# Board_R2_v2.net
KiCad netlist of a schematic drawn in EAGLE
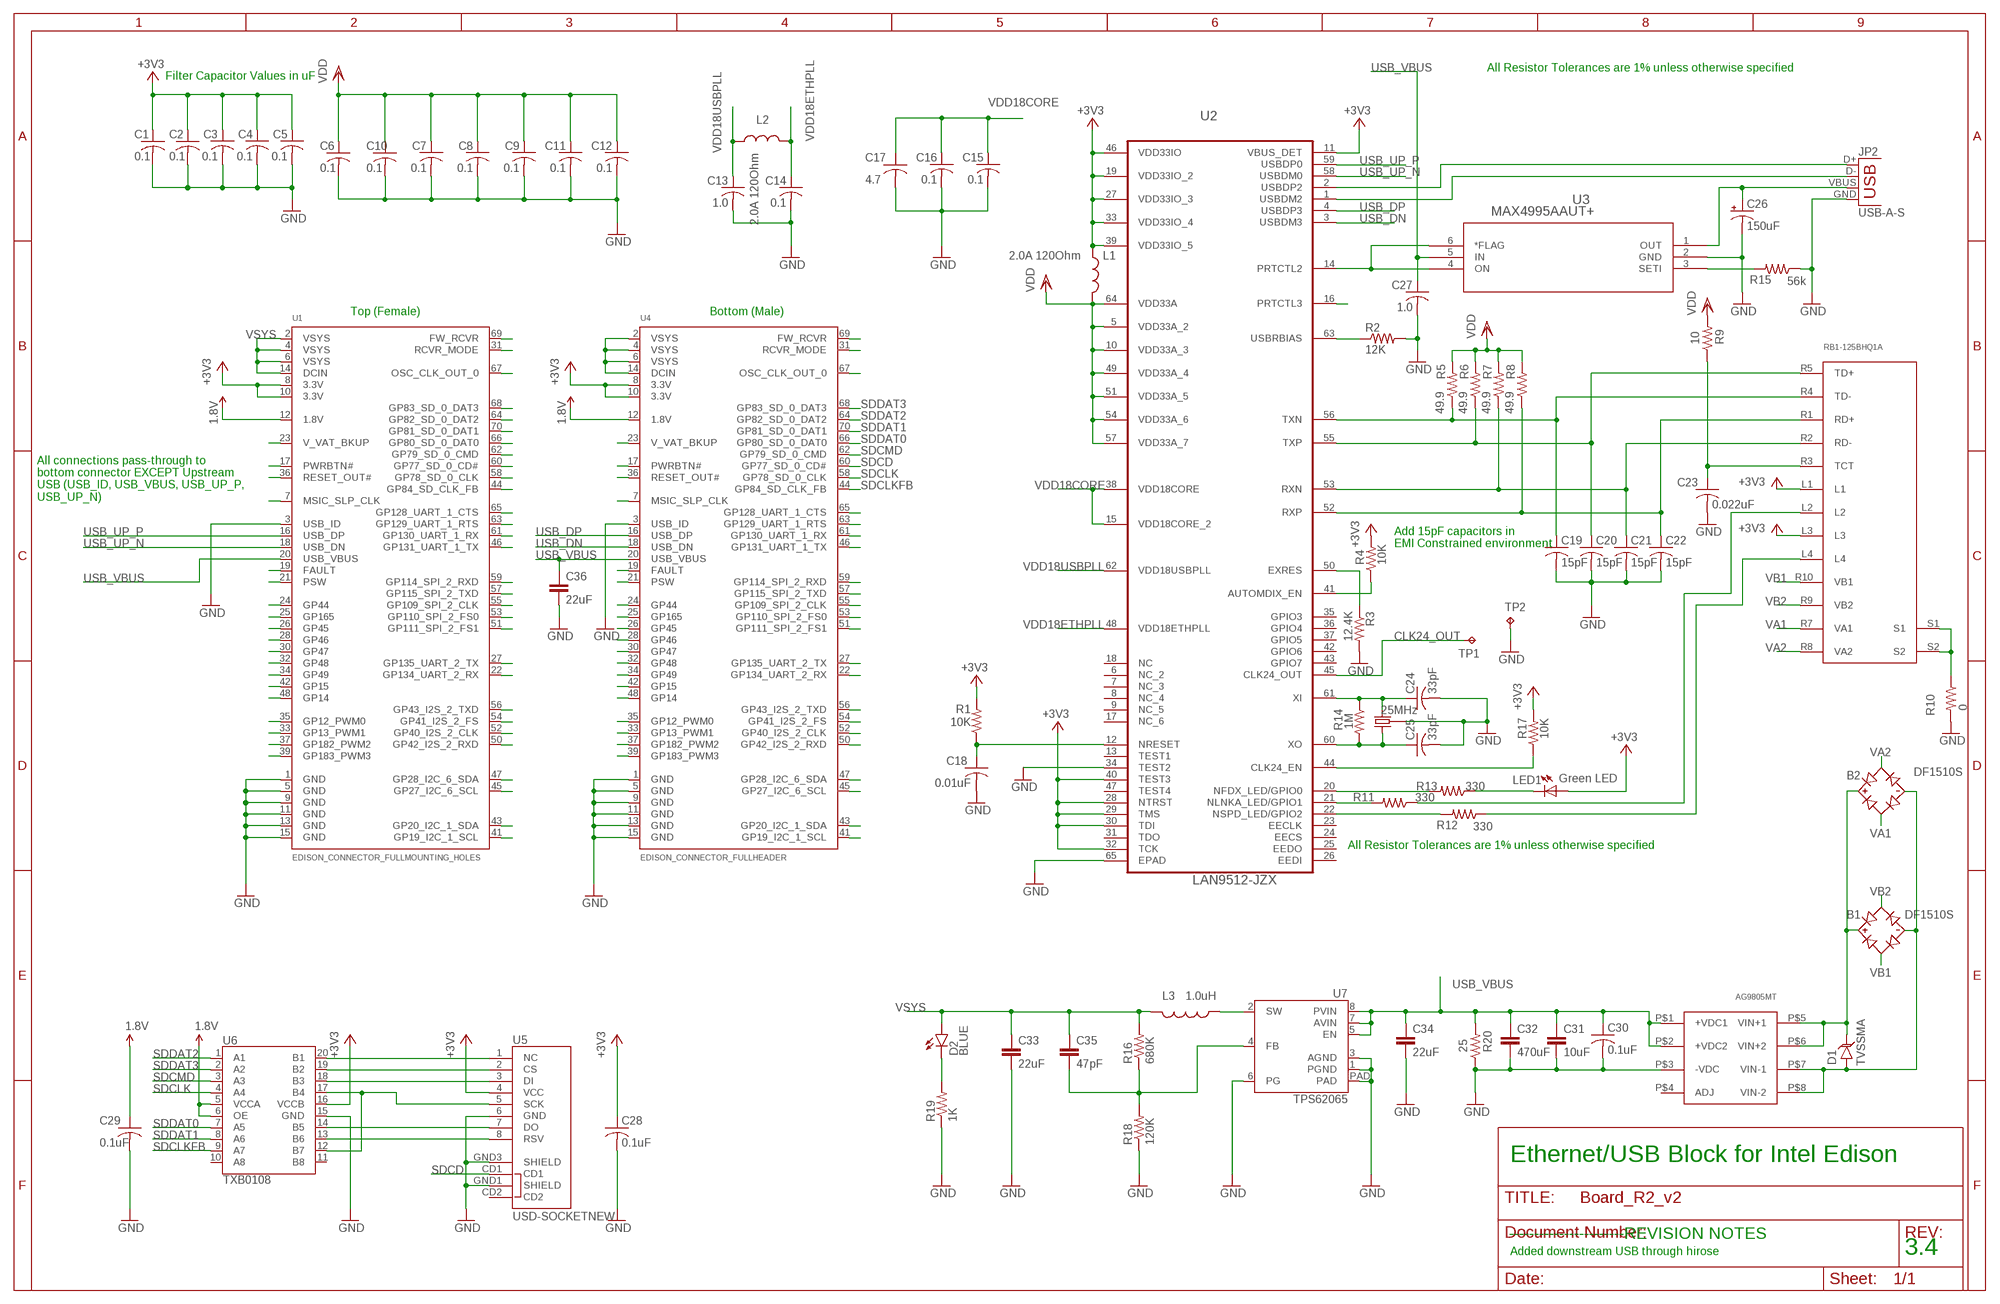
[diagram p0: schematic, sheet 1]

(export (version "E")
  (design (tool "Eeschema 10.0.6"))
  (components
    (comp (ref "AG9805MT")
      (value "AG9800M")
      (footprint "eagle-import:AG9800M_SMT")
      (libsource (lib "eagle-import") (part "AG9800M"))
    )
    (comp (ref "B1")
      (value "DF1510S")
      (footprint "eagle-import:DFS")
      (libsource (lib "eagle-import") (part "DF1510S"))
    )
    (comp (ref "B2")
      (value "DF1510S")
      (footprint "eagle-import:DFS")
      (libsource (lib "eagle-import") (part "DF1510S"))
    )
    (comp (ref "C1")
      (value "0.1")
      (footprint "eagle-import:C0402K")
      (libsource (lib "eagle-import") (part "C-USC0402K"))
    )
    (comp (ref "C2")
      (value "0.1")
      (footprint "eagle-import:C0402K")
      (libsource (lib "eagle-import") (part "C-USC0402K"))
    )
    (comp (ref "C3")
      (value "0.1")
      (footprint "eagle-import:C0402K")
      (libsource (lib "eagle-import") (part "C-USC0402K"))
    )
    (comp (ref "C4")
      (value "0.1")
      (footprint "eagle-import:C0402K")
      (libsource (lib "eagle-import") (part "C-USC0402K"))
    )
    (comp (ref "C5")
      (value "0.1")
      (footprint "eagle-import:C0402K")
      (libsource (lib "eagle-import") (part "C-USC0402K"))
    )
    (comp (ref "C6")
      (value "0.1")
      (footprint "eagle-import:C0402K")
      (libsource (lib "eagle-import") (part "C-USC0402K"))
    )
    (comp (ref "C7")
      (value "0.1")
      (footprint "eagle-import:C0402K")
      (libsource (lib "eagle-import") (part "C-USC0402K"))
    )
    (comp (ref "C8")
      (value "0.1")
      (footprint "eagle-import:C0402K")
      (libsource (lib "eagle-import") (part "C-USC0402K"))
    )
    (comp (ref "C9")
      (value "0.1")
      (footprint "eagle-import:C0402K")
      (libsource (lib "eagle-import") (part "C-USC0402K"))
    )
    (comp (ref "C10")
      (value "0.1")
      (footprint "eagle-import:C0402K")
      (libsource (lib "eagle-import") (part "C-USC0402K"))
    )
    (comp (ref "C11")
      (value "0.1")
      (footprint "eagle-import:C0402K")
      (libsource (lib "eagle-import") (part "C-USC0402K"))
    )
    (comp (ref "C12")
      (value "0.1")
      (footprint "eagle-import:C0402K")
      (libsource (lib "eagle-import") (part "C-USC0402K"))
    )
    (comp (ref "C13")
      (value "1.0")
      (footprint "eagle-import:C0402K")
      (libsource (lib "eagle-import") (part "C-USC0402K"))
    )
    (comp (ref "C14")
      (value "0.1")
      (footprint "eagle-import:C0402K")
      (libsource (lib "eagle-import") (part "C-USC0402K"))
    )
    (comp (ref "C15")
      (value "0.1")
      (footprint "eagle-import:C0402K")
      (libsource (lib "eagle-import") (part "C-USC0402K"))
    )
    (comp (ref "C16")
      (value "0.1")
      (footprint "eagle-import:C0402K")
      (libsource (lib "eagle-import") (part "C-USC0402K"))
    )
    (comp (ref "C17")
      (value "4.7")
      (footprint "eagle-import:C0603K")
      (libsource (lib "eagle-import") (part "C-USC0603K"))
    )
    (comp (ref "C18")
      (value "0.01uF")
      (footprint "eagle-import:C0603K")
      (libsource (lib "eagle-import") (part "C-USC0603K"))
    )
    (comp (ref "C19")
      (value "15pF")
      (footprint "eagle-import:C0402")
      (libsource (lib "eagle-import") (part "C-USC0402"))
    )
    (comp (ref "C20")
      (value "15pF")
      (footprint "eagle-import:C0402")
      (libsource (lib "eagle-import") (part "C-USC0402"))
    )
    (comp (ref "C21")
      (value "15pF")
      (footprint "eagle-import:C0402")
      (libsource (lib "eagle-import") (part "C-USC0402"))
    )
    (comp (ref "C22")
      (value "15pF")
      (footprint "eagle-import:C0402")
      (libsource (lib "eagle-import") (part "C-USC0402"))
    )
    (comp (ref "C23")
      (value "0.022uF")
      (footprint "eagle-import:C0805")
      (libsource (lib "eagle-import") (part "resistor_C-USC0805"))
    )
    (comp (ref "C24")
      (value "33pF")
      (footprint "eagle-import:C0402")
      (libsource (lib "eagle-import") (part "C-USC0402"))
    )
    (comp (ref "C25")
      (value "33pF")
      (footprint "eagle-import:C0402")
      (libsource (lib "eagle-import") (part "C-USC0402"))
    )
    (comp (ref "C26")
      (value "150uF")
      (footprint "eagle-import:PANASONIC_E")
      (libsource (lib "eagle-import") (part "CAP_POLE"))
    )
    (comp (ref "C27")
      (value "1.0")
      (footprint "eagle-import:C0402K")
      (libsource (lib "eagle-import") (part "C-USC0402K"))
    )
    (comp (ref "C28")
      (value "0.1uF")
      (footprint "eagle-import:C0402")
      (libsource (lib "eagle-import") (part "C-USC0402"))
    )
    (comp (ref "C29")
      (value "0.1uF")
      (footprint "eagle-import:C0402")
      (libsource (lib "eagle-import") (part "C-USC0402"))
    )
    (comp (ref "C30")
      (value "0.1uF")
      (footprint "eagle-import:C0402")
      (libsource (lib "eagle-import") (part "C-USC0402"))
    )
    (comp (ref "C31")
      (value "10uF")
      (footprint "eagle-import:1206-CAP")
      (libsource (lib "eagle-import") (part "4.7UF-16V-20%,+80%-(1206)"))
    )
    (comp (ref "C32")
      (value "470uF")
      (footprint "eagle-import:16SVPE470M")
      (libsource (lib "eagle-import") (part "F12CAP"))
    )
    (comp (ref "C33")
      (value "22uF")
      (footprint "eagle-import:0603-CAP")
      (libsource (lib "eagle-import") (part "47PF-50V-5%(0603)"))
    )
    (comp (ref "C34")
      (value "22uF")
      (footprint "eagle-import:0603-CAP")
      (libsource (lib "eagle-import") (part "47PF-50V-5%(0603)"))
    )
    (comp (ref "C35")
      (value "47pF")
      (footprint "eagle-import:0603-CAP")
      (libsource (lib "eagle-import") (part "47PF-50V-5%(0603)"))
    )
    (comp (ref "C36")
      (value "22uF")
      (footprint "eagle-import:0603-CAP")
      (libsource (lib "eagle-import") (part "47PF-50V-5%(0603)"))
    )
    (comp (ref "D1")
      (value "TVSSMA")
      (footprint "eagle-import:SMA-DIODE")
      (libsource (lib "eagle-import") (part "TVSSMA"))
    )
    (comp (ref "D2")
      (value "BLUE")
      (footprint "eagle-import:LED-0603")
      (libsource (lib "eagle-import") (part "LED-BLUE0603"))
    )
    (comp (ref "JP2")
      (value "USB-A-S")
      (footprint "eagle-import:USB-A-S")
      (libsource (lib "eagle-import") (part "USB-A-S"))
    )
    (comp (ref "L1")
      (value "2.0A 120Ohm")
      (footprint "eagle-import:L0603")
      (libsource (lib "eagle-import") (part "L-US0603"))
    )
    (comp (ref "L2")
      (value "2.0A 120Ohm")
      (footprint "eagle-import:L0603")
      (libsource (lib "eagle-import") (part "L-US0603"))
    )
    (comp (ref "L3")
      (value "1.0uH")
      (footprint "eagle-import:1210")
      (libsource (lib "eagle-import") (part "INDUCTOR1210"))
    )
    (comp (ref "LED1")
      (value "Green LED")
      (footprint "eagle-import:CHIP-LED0805")
      (libsource (lib "eagle-import") (part "LEDCHIP-LED0805"))
    )
    (comp (ref "R1")
      (value "10K")
      (footprint "eagle-import:R0603")
      (libsource (lib "eagle-import") (part "resistor_R-US_R0603"))
    )
    (comp (ref "R2")
      (value "12K")
      (footprint "eagle-import:R0603")
      (libsource (lib "eagle-import") (part "resistor_R-US_R0603"))
    )
    (comp (ref "R3")
      (value "12.4K")
      (footprint "eagle-import:R0603")
      (libsource (lib "eagle-import") (part "resistor_R-US_R0603"))
    )
    (comp (ref "R4")
      (value "10K")
      (footprint "eagle-import:R0603")
      (libsource (lib "eagle-import") (part "resistor_R-US_R0603"))
    )
    (comp (ref "R5")
      (value "49.9")
      (footprint "eagle-import:R0402")
      (libsource (lib "eagle-import") (part "resistor_R-US_R0402"))
    )
    (comp (ref "R6")
      (value "49.9")
      (footprint "eagle-import:R0402")
      (libsource (lib "eagle-import") (part "resistor_R-US_R0402"))
    )
    (comp (ref "R7")
      (value "49.9")
      (footprint "eagle-import:R0402")
      (libsource (lib "eagle-import") (part "resistor_R-US_R0402"))
    )
    (comp (ref "R8")
      (value "49.9")
      (footprint "eagle-import:R0402")
      (libsource (lib "eagle-import") (part "resistor_R-US_R0402"))
    )
    (comp (ref "R9")
      (value "10")
      (footprint "eagle-import:R0402")
      (libsource (lib "eagle-import") (part "resistor_R-US_R0402"))
    )
    (comp (ref "R10")
      (value "0")
      (footprint "eagle-import:R1210")
      (libsource (lib "eagle-import") (part "resistor_R-US_R1210"))
    )
    (comp (ref "R11")
      (value "330")
      (footprint "eagle-import:R0402")
      (libsource (lib "eagle-import") (part "resistor_R-US_R0402"))
    )
    (comp (ref "R12")
      (value "330")
      (footprint "eagle-import:R0402")
      (libsource (lib "eagle-import") (part "resistor_R-US_R0402"))
    )
    (comp (ref "R13")
      (value "330")
      (footprint "eagle-import:R0402")
      (libsource (lib "eagle-import") (part "resistor_R-US_R0402"))
    )
    (comp (ref "R14")
      (value "1M")
      (footprint "eagle-import:R0402")
      (libsource (lib "eagle-import") (part "resistor_R-US_R0402"))
    )
    (comp (ref "R15")
      (value "56k")
      (footprint "eagle-import:R0603")
      (libsource (lib "eagle-import") (part "R-US_R0603"))
    )
    (comp (ref "R16")
      (value "680K")
      (footprint "eagle-import:0402-RES")
      (libsource (lib "eagle-import") (part "RESISTOR0402"))
    )
    (comp (ref "R17")
      (value "10K")
      (footprint "eagle-import:R0603")
      (libsource (lib "eagle-import") (part "resistor_R-US_R0603"))
    )
    (comp (ref "R18")
      (value "120K")
      (footprint "eagle-import:0402-RES")
      (libsource (lib "eagle-import") (part "RESISTOR0402"))
    )
    (comp (ref "R19")
      (value "1K")
      (footprint "eagle-import:0603-RES")
      (libsource (lib "eagle-import") (part "1KOHM-1/10W-1%(0603)"))
    )
    (comp (ref "R20")
      (value "25")
      (footprint "eagle-import:R0402")
      (libsource (lib "eagle-import") (part "resistor_R-US_R0402"))
    )
    (comp (ref "RB1-125BHQ1A")
      (value "RB1-125BHQ1A")
      (footprint "eagle-import:RB1-125BHQ1A")
      (libsource (lib "eagle-import") (part "RB1-125BHQ1A"))
    )
    (comp (ref "TP1")
      (value "TPTP20R")
      (footprint "eagle-import:TP20R")
      (libsource (lib "eagle-import") (part "TPTP20R"))
    )
    (comp (ref "TP2")
      (value "TPTP20R")
      (footprint "eagle-import:TP20R")
      (libsource (lib "eagle-import") (part "TPTP20R"))
    )
    (comp (ref "U$1")
      (value "25MHz")
      (footprint "eagle-import:CRYSTAL-SMD-5X3")
      (libsource (lib "eagle-import") (part "CRYSTAL-GROUNDED"))
    )
    (comp (ref "U1")
      (value "EDISON_CONNECTOR_FULLMOUNTING_HOLES")
      (footprint "eagle-import:EDISON_DAUGHTER")
      (libsource (lib "eagle-import") (part "EDISON_CONNECTOR_FULLMOUNTING_HOLES"))
    )
    (comp (ref "U2")
      (value "LAN9512-JZX")
      (footprint "eagle-import:QFN50P900X900X100-65N")
      (libsource (lib "eagle-import") (part "LAN9512-JZX"))
    )
    (comp (ref "U3")
      (value "MAX4995AAUT+")
      (footprint "eagle-import:21-0058I")
      (fields (field (name "MANUFACTURER_PART_NUMBER") "max4995aaut+"))
      (libsource (lib "eagle-import") (part "MAX4995AAUT+"))
    )
    (comp (ref "U4")
      (value "EDISON_CONNECTOR_FULLHEADER")
      (footprint "eagle-import:DF40C-70DP-0.4(51)")
      (libsource (lib "eagle-import") (part "EDISON_CONNECTOR_FULLHEADER"))
    )
    (comp (ref "U5")
      (value "USD-SOCKETNEW")
      (footprint "eagle-import:MICRO-SD-SOCKET-PP")
      (libsource (lib "eagle-import") (part "USD-SOCKETNEW"))
    )
    (comp (ref "U6")
      (value "TXB0108")
      (footprint "eagle-import:UFDFN-20")
      (libsource (lib "eagle-import") (part "TXB0108"))
    )
    (comp (ref "U7")
      (value "TPS62065")
      (footprint "eagle-import:WSON-8-PAD")
      (libsource (lib "eagle-import") (part "TPS62065"))
    )
  )
  (nets
    (net (code "1") (name "+3V3") (class "Default")
      (node (ref "C1") (pin "1") (pinfunction "1_1") (pintype "passive"))
      (node (ref "C2") (pin "1") (pinfunction "1_1") (pintype "passive"))
      (node (ref "C28") (pin "1") (pinfunction "1_1") (pintype "passive"))
      (node (ref "C3") (pin "1") (pinfunction "1_1") (pintype "passive"))
      (node (ref "C4") (pin "1") (pinfunction "1_1") (pintype "passive"))
      (node (ref "C5") (pin "1") (pinfunction "1_1") (pintype "passive"))
      (node (ref "L1") (pin "1") (pinfunction "1_1") (pintype "passive"))
      (node (ref "LED1") (pin "A") (pinfunction "A_A") (pintype "passive"))
      (node (ref "R1") (pin "2") (pinfunction "2_2") (pintype "passive"))
      (node (ref "R17") (pin "2") (pinfunction "2_2") (pintype "passive"))
      (node (ref "R4") (pin "2") (pinfunction "2_2") (pintype "passive"))
      (node (ref "RB1-125BHQ1A") (pin "L1") (pinfunction "L1_L1") (pintype "input"))
      (node (ref "RB1-125BHQ1A") (pin "L3") (pinfunction "L3_L3") (pintype "input"))
      (node (ref "U1") (pin "10") (pinfunction "3.3V_10") (pintype "bidirectional"))
      (node (ref "U1") (pin "8") (pinfunction "3.3V_8") (pintype "bidirectional"))
      (node (ref "U2") (pin "11") (pinfunction "VBUS_DET_11") (pintype "power_in"))
      (node (ref "U2") (pin "19") (pinfunction "VDD33IO_2_19") (pintype "power_in"))
      (node (ref "U2") (pin "27") (pinfunction "VDD33IO_3_27") (pintype "power_in"))
      (node (ref "U2") (pin "28") (pinfunction "NTRST_28") (pintype "passive"))
      (node (ref "U2") (pin "29") (pinfunction "TMS_29") (pintype "passive"))
      (node (ref "U2") (pin "30") (pinfunction "TDI_30") (pintype "passive"))
      (node (ref "U2") (pin "32") (pinfunction "TCK_32") (pintype "passive"))
      (node (ref "U2") (pin "33") (pinfunction "VDD33IO_4_33") (pintype "power_in"))
      (node (ref "U2") (pin "39") (pinfunction "VDD33IO_5_39") (pintype "power_in"))
      (node (ref "U2") (pin "40") (pinfunction "TEST3_40") (pintype "passive"))
      (node (ref "U2") (pin "46") (pinfunction "VDD33IO_46") (pintype "power_in"))
      (node (ref "U4") (pin "10") (pinfunction "3.3V_10") (pintype "bidirectional"))
      (node (ref "U4") (pin "8") (pinfunction "3.3V_8") (pintype "bidirectional"))
      (node (ref "U5") (pin "4") (pinfunction "VCC_4") (pintype "bidirectional"))
      (node (ref "U6") (pin "16") (pinfunction "VCCB_16") (pintype "bidirectional"))
    )
    (net (code "2") (name "/CLK24_OUT") (class "Default")
      (node (ref "TP1") (pin "TP") (pinfunction "TP_TP") (pintype "input"))
      (node (ref "U2") (pin "45") (pinfunction "CLK24_OUT_45") (pintype "passive"))
    )
    (net (code "3") (name "/P7") (class "Default")
      (node (ref "U1") (pin "7") (pinfunction "MSIC_SLP_CLK_7") (pintype "bidirectional"))
      (node (ref "U4") (pin "7") (pinfunction "MSIC_SLP_CLK_7") (pintype "bidirectional"))
    )
    (net (code "4") (name "/P17") (class "Default")
      (node (ref "U1") (pin "17") (pinfunction "PWRBTN#_17") (pintype "bidirectional"))
      (node (ref "U4") (pin "17") (pinfunction "PWRBTN#_17") (pintype "bidirectional"))
    )
    (net (code "5") (name "/P19") (class "Default")
      (node (ref "U1") (pin "19") (pinfunction "FAULT_19") (pintype "bidirectional"))
      (node (ref "U4") (pin "19") (pinfunction "FAULT_19") (pintype "bidirectional"))
    )
    (net (code "6") (name "/P21") (class "Default")
      (node (ref "U1") (pin "21") (pinfunction "PSW_21") (pintype "bidirectional"))
      (node (ref "U4") (pin "21") (pinfunction "PSW_21") (pintype "bidirectional"))
    )
    (net (code "7") (name "/P22") (class "Default")
      (node (ref "U1") (pin "22") (pinfunction "GP134_UART_2_RX_22") (pintype "bidirectional"))
      (node (ref "U4") (pin "22") (pinfunction "GP134_UART_2_RX_22") (pintype "bidirectional"))
    )
    (net (code "8") (name "/P23") (class "Default")
      (node (ref "U1") (pin "23") (pinfunction "V_VAT_BKUP_23") (pintype "bidirectional"))
      (node (ref "U4") (pin "23") (pinfunction "V_VAT_BKUP_23") (pintype "bidirectional"))
    )
    (net (code "9") (name "/P24") (class "Default")
      (node (ref "U1") (pin "24") (pinfunction "GP44_24") (pintype "bidirectional"))
      (node (ref "U4") (pin "24") (pinfunction "GP44_24") (pintype "bidirectional"))
    )
    (net (code "10") (name "/P25") (class "Default")
      (node (ref "U1") (pin "25") (pinfunction "GP165_25") (pintype "bidirectional"))
      (node (ref "U4") (pin "25") (pinfunction "GP165_25") (pintype "bidirectional"))
    )
    (net (code "11") (name "/P26") (class "Default")
      (node (ref "U1") (pin "26") (pinfunction "GP45_26") (pintype "bidirectional"))
      (node (ref "U4") (pin "26") (pinfunction "GP45_26") (pintype "bidirectional"))
    )
    (net (code "12") (name "/P27") (class "Default")
      (node (ref "U1") (pin "27") (pinfunction "GP135_UART_2_TX_27") (pintype "bidirectional"))
      (node (ref "U4") (pin "27") (pinfunction "GP135_UART_2_TX_27") (pintype "bidirectional"))
    )
    (net (code "13") (name "/P28") (class "Default")
      (node (ref "U1") (pin "28") (pinfunction "GP46_28") (pintype "bidirectional"))
      (node (ref "U4") (pin "28") (pinfunction "GP46_28") (pintype "bidirectional"))
    )
    (net (code "14") (name "/P30") (class "Default")
      (node (ref "U1") (pin "30") (pinfunction "GP47_30") (pintype "bidirectional"))
      (node (ref "U4") (pin "30") (pinfunction "GP47_30") (pintype "bidirectional"))
    )
    (net (code "15") (name "/P31") (class "Default")
      (node (ref "U1") (pin "31") (pinfunction "RCVR_MODE_31") (pintype "bidirectional"))
      (node (ref "U4") (pin "31") (pinfunction "RCVR_MODE_31") (pintype "bidirectional"))
    )
    (net (code "16") (name "/P32") (class "Default")
      (node (ref "U1") (pin "32") (pinfunction "GP48_32") (pintype "bidirectional"))
      (node (ref "U4") (pin "32") (pinfunction "GP48_32") (pintype "bidirectional"))
    )
    (net (code "17") (name "/P33") (class "Default")
      (node (ref "U1") (pin "33") (pinfunction "GP13_PWM1_33") (pintype "bidirectional"))
      (node (ref "U4") (pin "33") (pinfunction "GP13_PWM1_33") (pintype "bidirectional"))
    )
    (net (code "18") (name "/P34") (class "Default")
      (node (ref "U1") (pin "34") (pinfunction "GP49_34") (pintype "bidirectional"))
      (node (ref "U4") (pin "34") (pinfunction "GP49_34") (pintype "bidirectional"))
    )
    (net (code "19") (name "/P35") (class "Default")
      (node (ref "U1") (pin "35") (pinfunction "GP12_PWM0_35") (pintype "bidirectional"))
      (node (ref "U4") (pin "35") (pinfunction "GP12_PWM0_35") (pintype "bidirectional"))
    )
    (net (code "20") (name "/P36") (class "Default")
      (node (ref "U1") (pin "36") (pinfunction "RESET_OUT#_36") (pintype "bidirectional"))
      (node (ref "U4") (pin "36") (pinfunction "RESET_OUT#_36") (pintype "bidirectional"))
    )
    (net (code "21") (name "/P37") (class "Default")
      (node (ref "U1") (pin "37") (pinfunction "GP182_PWM2_37") (pintype "bidirectional"))
      (node (ref "U4") (pin "37") (pinfunction "GP182_PWM2_37") (pintype "bidirectional"))
    )
    (net (code "22") (name "/P39") (class "Default")
      (node (ref "U1") (pin "39") (pinfunction "GP183_PWM3_39") (pintype "bidirectional"))
      (node (ref "U4") (pin "39") (pinfunction "GP183_PWM3_39") (pintype "bidirectional"))
    )
    (net (code "23") (name "/P41") (class "Default")
      (node (ref "U1") (pin "41") (pinfunction "GP19_I2C_1_SCL_41") (pintype "bidirectional"))
      (node (ref "U4") (pin "41") (pinfunction "GP19_I2C_1_SCL_41") (pintype "bidirectional"))
    )
    (net (code "24") (name "/P42") (class "Default")
      (node (ref "U1") (pin "42") (pinfunction "GP15_42") (pintype "bidirectional"))
      (node (ref "U4") (pin "42") (pinfunction "GP15_42") (pintype "bidirectional"))
    )
    (net (code "25") (name "/P43") (class "Default")
      (node (ref "U1") (pin "43") (pinfunction "GP20_I2C_1_SDA_43") (pintype "bidirectional"))
      (node (ref "U4") (pin "43") (pinfunction "GP20_I2C_1_SDA_43") (pintype "bidirectional"))
    )
    (net (code "26") (name "/P45") (class "Default")
      (node (ref "U1") (pin "45") (pinfunction "GP27_I2C_6_SCL_45") (pintype "bidirectional"))
      (node (ref "U4") (pin "45") (pinfunction "GP27_I2C_6_SCL_45") (pintype "bidirectional"))
    )
    (net (code "27") (name "/P46") (class "Default")
      (node (ref "U1") (pin "46") (pinfunction "GP131_UART_1_TX_46") (pintype "bidirectional"))
      (node (ref "U4") (pin "46") (pinfunction "GP131_UART_1_TX_46") (pintype "bidirectional"))
    )
    (net (code "28") (name "/P47") (class "Default")
      (node (ref "U1") (pin "47") (pinfunction "GP28_I2C_6_SDA_47") (pintype "bidirectional"))
      (node (ref "U4") (pin "47") (pinfunction "GP28_I2C_6_SDA_47") (pintype "bidirectional"))
    )
    (net (code "29") (name "/P48") (class "Default")
      (node (ref "U1") (pin "48") (pinfunction "GP14_48") (pintype "bidirectional"))
      (node (ref "U4") (pin "48") (pinfunction "GP14_48") (pintype "bidirectional"))
    )
    (net (code "30") (name "/P50") (class "Default")
      (node (ref "U1") (pin "50") (pinfunction "GP42_I2S_2_RXD_50") (pintype "bidirectional"))
      (node (ref "U4") (pin "50") (pinfunction "GP42_I2S_2_RXD_50") (pintype "bidirectional"))
    )
    (net (code "31") (name "/P51") (class "Default")
      (node (ref "U1") (pin "51") (pinfunction "GP111_SPI_2_FS1_51") (pintype "bidirectional"))
      (node (ref "U4") (pin "51") (pinfunction "GP111_SPI_2_FS1_51") (pintype "bidirectional"))
    )
    (net (code "32") (name "/P52") (class "Default")
      (node (ref "U1") (pin "52") (pinfunction "GP40_I2S_2_CLK_52") (pintype "bidirectional"))
      (node (ref "U4") (pin "52") (pinfunction "GP40_I2S_2_CLK_52") (pintype "bidirectional"))
    )
    (net (code "33") (name "/P53") (class "Default")
      (node (ref "U1") (pin "53") (pinfunction "GP110_SPI_2_FS0_53") (pintype "bidirectional"))
      (node (ref "U4") (pin "53") (pinfunction "GP110_SPI_2_FS0_53") (pintype "bidirectional"))
    )
    (net (code "34") (name "/P54") (class "Default")
      (node (ref "U1") (pin "54") (pinfunction "GP41_I2S_2_FS_54") (pintype "bidirectional"))
      (node (ref "U4") (pin "54") (pinfunction "GP41_I2S_2_FS_54") (pintype "bidirectional"))
    )
    (net (code "35") (name "/P55") (class "Default")
      (node (ref "U1") (pin "55") (pinfunction "GP109_SPI_2_CLK_55") (pintype "bidirectional"))
      (node (ref "U4") (pin "55") (pinfunction "GP109_SPI_2_CLK_55") (pintype "bidirectional"))
    )
    (net (code "36") (name "/P56") (class "Default")
      (node (ref "U1") (pin "56") (pinfunction "GP43_I2S_2_TXD_56") (pintype "bidirectional"))
      (node (ref "U4") (pin "56") (pinfunction "GP43_I2S_2_TXD_56") (pintype "bidirectional"))
    )
    (net (code "37") (name "/P57") (class "Default")
      (node (ref "U1") (pin "57") (pinfunction "GP115_SPI_2_TXD_57") (pintype "bidirectional"))
      (node (ref "U4") (pin "57") (pinfunction "GP115_SPI_2_TXD_57") (pintype "bidirectional"))
    )
    (net (code "38") (name "/P59") (class "Default")
      (node (ref "U1") (pin "59") (pinfunction "GP114_SPI_2_RXD_59") (pintype "bidirectional"))
      (node (ref "U4") (pin "59") (pinfunction "GP114_SPI_2_RXD_59") (pintype "bidirectional"))
    )
    (net (code "39") (name "/P61") (class "Default")
      (node (ref "U1") (pin "61") (pinfunction "GP130_UART_1_RX_61") (pintype "bidirectional"))
      (node (ref "U4") (pin "61") (pinfunction "GP130_UART_1_RX_61") (pintype "bidirectional"))
    )
    (net (code "40") (name "/P63") (class "Default")
      (node (ref "U1") (pin "63") (pinfunction "GP129_UART_1_RTS_63") (pintype "bidirectional"))
      (node (ref "U4") (pin "63") (pinfunction "GP129_UART_1_RTS_63") (pintype "bidirectional"))
    )
    (net (code "41") (name "/P65") (class "Default")
      (node (ref "U1") (pin "65") (pinfunction "GP128_UART_1_CTS_65") (pintype "bidirectional"))
      (node (ref "U4") (pin "65") (pinfunction "GP128_UART_1_CTS_65") (pintype "bidirectional"))
    )
    (net (code "42") (name "/P67") (class "Default")
      (node (ref "U1") (pin "67") (pinfunction "OSC_CLK_OUT_0_67") (pintype "bidirectional"))
      (node (ref "U4") (pin "67") (pinfunction "OSC_CLK_OUT_0_67") (pintype "bidirectional"))
    )
    (net (code "43") (name "/P69") (class "Default")
      (node (ref "U1") (pin "69") (pinfunction "FW_RCVR_69") (pintype "bidirectional"))
      (node (ref "U4") (pin "69") (pinfunction "FW_RCVR_69") (pintype "bidirectional"))
    )
    (net (code "44") (name "/SDCD") (class "Default")
      (node (ref "U1") (pin "60") (pinfunction "GP77_SD_0_CD#_60") (pintype "bidirectional"))
      (node (ref "U4") (pin "60") (pinfunction "GP77_SD_0_CD#_60") (pintype "bidirectional"))
      (node (ref "U5") (pin "CD1") (pinfunction "CD1_CD1") (pintype "bidirectional"))
    )
    (net (code "45") (name "/SDCLK") (class "Default")
      (node (ref "U1") (pin "58") (pinfunction "GP78_SD_0_CLK_58") (pintype "bidirectional"))
      (node (ref "U4") (pin "58") (pinfunction "GP78_SD_0_CLK_58") (pintype "bidirectional"))
      (node (ref "U6") (pin "4") (pinfunction "A4_4") (pintype "bidirectional"))
    )
    (net (code "46") (name "/SDCLKFB") (class "Default")
      (node (ref "U1") (pin "44") (pinfunction "GP84_SD_CLK_FB_44") (pintype "bidirectional"))
      (node (ref "U4") (pin "44") (pinfunction "GP84_SD_CLK_FB_44") (pintype "bidirectional"))
      (node (ref "U6") (pin "9") (pinfunction "A7_9") (pintype "bidirectional"))
    )
    (net (code "47") (name "/SDCMD") (class "Default")
      (node (ref "U1") (pin "62") (pinfunction "GP79_SD_0_CMD_62") (pintype "bidirectional"))
      (node (ref "U4") (pin "62") (pinfunction "GP79_SD_0_CMD_62") (pintype "bidirectional"))
      (node (ref "U6") (pin "3") (pinfunction "A3_3") (pintype "bidirectional"))
    )
    (net (code "48") (name "/SDDAT0") (class "Default")
      (node (ref "U1") (pin "66") (pinfunction "GP80_SD_0_DAT0_66") (pintype "bidirectional"))
      (node (ref "U4") (pin "66") (pinfunction "GP80_SD_0_DAT0_66") (pintype "bidirectional"))
      (node (ref "U6") (pin "7") (pinfunction "A5_7") (pintype "bidirectional"))
    )
    (net (code "49") (name "/SDDAT1") (class "Default")
      (node (ref "U1") (pin "70") (pinfunction "GP81_SD_0_DAT1_70") (pintype "bidirectional"))
      (node (ref "U4") (pin "70") (pinfunction "GP81_SD_0_DAT1_70") (pintype "bidirectional"))
      (node (ref "U6") (pin "8") (pinfunction "A6_8") (pintype "bidirectional"))
    )
    (net (code "50") (name "/SDDAT2") (class "Default")
      (node (ref "U1") (pin "64") (pinfunction "GP82_SD_0_DAT2_64") (pintype "bidirectional"))
      (node (ref "U4") (pin "64") (pinfunction "GP82_SD_0_DAT2_64") (pintype "bidirectional"))
      (node (ref "U6") (pin "1") (pinfunction "A1_1") (pintype "bidirectional"))
    )
    (net (code "51") (name "/SDDAT3") (class "Default")
      (node (ref "U1") (pin "68") (pinfunction "GP83_SD_0_DAT3_68") (pintype "bidirectional"))
      (node (ref "U4") (pin "68") (pinfunction "GP83_SD_0_DAT3_68") (pintype "bidirectional"))
      (node (ref "U6") (pin "2") (pinfunction "A2_2") (pintype "bidirectional"))
    )
    (net (code "52") (name "/USB_DN") (class "Default")
      (node (ref "U2") (pin "3") (pinfunction "USBDM3_3") (pintype "passive"))
      (node (ref "U4") (pin "18") (pinfunction "USB_DN_18") (pintype "bidirectional"))
    )
    (net (code "53") (name "/USB_DP") (class "Default")
      (node (ref "U2") (pin "4") (pinfunction "USBDP3_4") (pintype "passive"))
      (node (ref "U4") (pin "16") (pinfunction "USB_DP_16") (pintype "bidirectional"))
    )
    (net (code "54") (name "/USB_UP_N") (class "Default")
      (node (ref "U1") (pin "18") (pinfunction "USB_DN_18") (pintype "bidirectional"))
      (node (ref "U2") (pin "58") (pinfunction "USBDM0_58") (pintype "passive"))
    )
    (net (code "55") (name "/USB_UP_P") (class "Default")
      (node (ref "U1") (pin "16") (pinfunction "USB_DP_16") (pintype "bidirectional"))
      (node (ref "U2") (pin "59") (pinfunction "USBDP0_59") (pintype "passive"))
    )
    (net (code "56") (name "/USB_VBUS") (class "Default")
      (node (ref "AG9805MT") (pin "P$1") (pinfunction "+VDC1_P$1") (pintype "output"))
      (node (ref "AG9805MT") (pin "P$2") (pinfunction "+VDC2_P$2") (pintype "output"))
      (node (ref "C27") (pin "1") (pinfunction "1_1") (pintype "passive"))
      (node (ref "C30") (pin "1") (pinfunction "1_1") (pintype "passive"))
      (node (ref "C31") (pin "1") (pinfunction "1_1") (pintype "passive"))
      (node (ref "C32") (pin "1") (pinfunction "1_1") (pintype "passive"))
      (node (ref "C34") (pin "1") (pinfunction "1_1") (pintype "passive"))
      (node (ref "C36") (pin "1") (pinfunction "1_1") (pintype "passive"))
      (node (ref "R20") (pin "2") (pinfunction "2_2") (pintype "passive"))
      (node (ref "U1") (pin "20") (pinfunction "USB_VBUS_20") (pintype "bidirectional"))
      (node (ref "U3") (pin "5") (pinfunction "IN_5") (pintype "input"))
      (node (ref "U4") (pin "20") (pinfunction "USB_VBUS_20") (pintype "bidirectional"))
      (node (ref "U7") (pin "5") (pinfunction "EN_5") (pintype "bidirectional"))
      (node (ref "U7") (pin "7") (pinfunction "AVIN_7") (pintype "bidirectional"))
      (node (ref "U7") (pin "8") (pinfunction "PVIN_8") (pintype "bidirectional"))
    )
    (net (code "57") (name "/VA1") (class "Default")
      (node (ref "B2") (pin "~@1") (pinfunction "AC1_~@1") (pintype "passive"))
      (node (ref "RB1-125BHQ1A") (pin "R7") (pinfunction "VA1_R7") (pintype "output"))
    )
    (net (code "58") (name "/VA2") (class "Default")
      (node (ref "B2") (pin "~@2") (pinfunction "AC2_~@2") (pintype "passive"))
      (node (ref "RB1-125BHQ1A") (pin "R8") (pinfunction "VA2_R8") (pintype "output"))
    )
    (net (code "59") (name "/VB1") (class "Default")
      (node (ref "B1") (pin "~@1") (pinfunction "AC1_~@1") (pintype "passive"))
      (node (ref "RB1-125BHQ1A") (pin "R10") (pinfunction "VB1_R10") (pintype "output"))
    )
    (net (code "60") (name "/VB2") (class "Default")
      (node (ref "B1") (pin "~@2") (pinfunction "AC2_~@2") (pintype "passive"))
      (node (ref "RB1-125BHQ1A") (pin "R9") (pinfunction "VB2_R9") (pintype "output"))
    )
    (net (code "61") (name "/VDD18CORE") (class "Default")
      (node (ref "C15") (pin "1") (pinfunction "1_1") (pintype "passive"))
      (node (ref "C16") (pin "1") (pinfunction "1_1") (pintype "passive"))
      (node (ref "C17") (pin "1") (pinfunction "1_1") (pintype "passive"))
      (node (ref "U2") (pin "15") (pinfunction "VDD18CORE_2_15") (pintype "power_in"))
      (node (ref "U2") (pin "38") (pinfunction "VDD18CORE_38") (pintype "power_in"))
    )
    (net (code "62") (name "/VDD18ETHPLL") (class "Default")
      (node (ref "C14") (pin "1") (pinfunction "1_1") (pintype "passive"))
      (node (ref "L2") (pin "2") (pinfunction "2_2") (pintype "passive"))
      (node (ref "U2") (pin "48") (pinfunction "VDD18ETHPLL_48") (pintype "power_in"))
    )
    (net (code "63") (name "/VDD18USBPLL") (class "Default")
      (node (ref "C13") (pin "1") (pinfunction "1_1") (pintype "passive"))
      (node (ref "L2") (pin "1") (pinfunction "1_1") (pintype "passive"))
      (node (ref "U2") (pin "62") (pinfunction "VDD18USBPLL_62") (pintype "power_in"))
    )
    (net (code "64") (name "/VSYS") (class "Default")
      (node (ref "C33") (pin "1") (pinfunction "1_1") (pintype "passive"))
      (node (ref "C35") (pin "1") (pinfunction "1_1") (pintype "passive"))
      (node (ref "D2") (pin "A") (pinfunction "A_A") (pintype "passive"))
      (node (ref "L3") (pin "2") (pinfunction "2_2") (pintype "passive"))
      (node (ref "R16") (pin "2") (pinfunction "2_2") (pintype "passive"))
      (node (ref "U1") (pin "14") (pinfunction "DCIN_14") (pintype "bidirectional"))
      (node (ref "U1") (pin "2") (pinfunction "VSYS_2") (pintype "bidirectional"))
      (node (ref "U1") (pin "4") (pinfunction "VSYS_4") (pintype "bidirectional"))
      (node (ref "U1") (pin "6") (pinfunction "VSYS_6") (pintype "bidirectional"))
      (node (ref "U4") (pin "14") (pinfunction "DCIN_14") (pintype "bidirectional"))
      (node (ref "U4") (pin "2") (pinfunction "VSYS_2") (pintype "bidirectional"))
      (node (ref "U4") (pin "4") (pinfunction "VSYS_4") (pintype "bidirectional"))
      (node (ref "U4") (pin "6") (pinfunction "VSYS_6") (pintype "bidirectional"))
    )
    (net (code "65") (name "1.8V") (class "Default")
      (node (ref "C29") (pin "1") (pinfunction "1_1") (pintype "passive"))
      (node (ref "U1") (pin "12") (pinfunction "1.8V_12") (pintype "bidirectional"))
      (node (ref "U4") (pin "12") (pinfunction "1.8V_12") (pintype "bidirectional"))
      (node (ref "U6") (pin "5") (pinfunction "VCCA_5") (pintype "bidirectional"))
      (node (ref "U6") (pin "6") (pinfunction "OE_6") (pintype "bidirectional"))
    )
    (net (code "66") (name "GND") (class "Default")
      (node (ref "AG9805MT") (pin "P$3") (pinfunction "-VDC_P$3") (pintype "bidirectional"))
      (node (ref "C1") (pin "2") (pinfunction "2_2") (pintype "passive"))
      (node (ref "C10") (pin "2") (pinfunction "2_2") (pintype "passive"))
      (node (ref "C11") (pin "2") (pinfunction "2_2") (pintype "passive"))
      (node (ref "C12") (pin "2") (pinfunction "2_2") (pintype "passive"))
      (node (ref "C13") (pin "2") (pinfunction "2_2") (pintype "passive"))
      (node (ref "C14") (pin "2") (pinfunction "2_2") (pintype "passive"))
      (node (ref "C15") (pin "2") (pinfunction "2_2") (pintype "passive"))
      (node (ref "C16") (pin "2") (pinfunction "2_2") (pintype "passive"))
      (node (ref "C17") (pin "2") (pinfunction "2_2") (pintype "passive"))
      (node (ref "C18") (pin "2") (pinfunction "2_2") (pintype "passive"))
      (node (ref "C19") (pin "2") (pinfunction "2_2") (pintype "passive"))
      (node (ref "C2") (pin "2") (pinfunction "2_2") (pintype "passive"))
      (node (ref "C20") (pin "2") (pinfunction "2_2") (pintype "passive"))
      (node (ref "C21") (pin "2") (pinfunction "2_2") (pintype "passive"))
      (node (ref "C22") (pin "2") (pinfunction "2_2") (pintype "passive"))
      (node (ref "C23") (pin "2") (pinfunction "2_2") (pintype "passive"))
      (node (ref "C24") (pin "2") (pinfunction "2_2") (pintype "passive"))
      (node (ref "C25") (pin "2") (pinfunction "2_2") (pintype "passive"))
      (node (ref "C26") (pin "-") (pinfunction "-_-") (pintype "passive"))
      (node (ref "C27") (pin "2") (pinfunction "2_2") (pintype "passive"))
      (node (ref "C28") (pin "2") (pinfunction "2_2") (pintype "passive"))
      (node (ref "C29") (pin "2") (pinfunction "2_2") (pintype "passive"))
      (node (ref "C3") (pin "2") (pinfunction "2_2") (pintype "passive"))
      (node (ref "C30") (pin "2") (pinfunction "2_2") (pintype "passive"))
      (node (ref "C31") (pin "2") (pinfunction "2_2") (pintype "passive"))
      (node (ref "C32") (pin "2") (pinfunction "2_2") (pintype "passive"))
      (node (ref "C33") (pin "2") (pinfunction "2_2") (pintype "passive"))
      (node (ref "C34") (pin "2") (pinfunction "2_2") (pintype "passive"))
      (node (ref "C36") (pin "2") (pinfunction "2_2") (pintype "passive"))
      (node (ref "C4") (pin "2") (pinfunction "2_2") (pintype "passive"))
      (node (ref "C5") (pin "2") (pinfunction "2_2") (pintype "passive"))
      (node (ref "C6") (pin "2") (pinfunction "2_2") (pintype "passive"))
      (node (ref "C7") (pin "2") (pinfunction "2_2") (pintype "passive"))
      (node (ref "C8") (pin "2") (pinfunction "2_2") (pintype "passive"))
      (node (ref "C9") (pin "2") (pinfunction "2_2") (pintype "passive"))
      (node (ref "JP2") (pin "GND") (pinfunction "GND_GND") (pintype "bidirectional"))
      (node (ref "R10") (pin "2") (pinfunction "2_2") (pintype "passive"))
      (node (ref "R15") (pin "1") (pinfunction "1_1") (pintype "passive"))
      (node (ref "R18") (pin "1") (pinfunction "1_1") (pintype "passive"))
      (node (ref "R19") (pin "1") (pinfunction "1_1") (pintype "passive"))
      (node (ref "R2") (pin "2") (pinfunction "2_2") (pintype "passive"))
      (node (ref "R20") (pin "1") (pinfunction "1_1") (pintype "passive"))
      (node (ref "R3") (pin "2") (pinfunction "2_2") (pintype "passive"))
      (node (ref "TP2") (pin "TP") (pinfunction "TP_TP") (pintype "input"))
      (node (ref "U$1") (pin "2") (pinfunction "3_2") (pintype "passive"))
      (node (ref "U$1") (pin "4") (pinfunction "3_4") (pintype "passive"))
      (node (ref "U1") (pin "1") (pinfunction "GND_1") (pintype "bidirectional"))
      (node (ref "U1") (pin "11") (pinfunction "GND_11") (pintype "bidirectional"))
      (node (ref "U1") (pin "13") (pinfunction "GND_13") (pintype "bidirectional"))
      (node (ref "U1") (pin "15") (pinfunction "GND_15") (pintype "bidirectional"))
      (node (ref "U1") (pin "3") (pinfunction "USB_ID_3") (pintype "bidirectional"))
      (node (ref "U1") (pin "5") (pinfunction "GND_5") (pintype "bidirectional"))
      (node (ref "U1") (pin "9") (pinfunction "GND_9") (pintype "bidirectional"))
      (node (ref "U2") (pin "34") (pinfunction "TEST2_34") (pintype "passive"))
      (node (ref "U2") (pin "65") (pinfunction "EPAD_65") (pintype "passive"))
      (node (ref "U3") (pin "2") (pinfunction "GND_2") (pintype "power_in"))
      (node (ref "U4") (pin "1") (pinfunction "GND_1") (pintype "bidirectional"))
      (node (ref "U4") (pin "11") (pinfunction "GND_11") (pintype "bidirectional"))
      (node (ref "U4") (pin "13") (pinfunction "GND_13") (pintype "bidirectional"))
      (node (ref "U4") (pin "15") (pinfunction "GND_15") (pintype "bidirectional"))
      (node (ref "U4") (pin "3") (pinfunction "USB_ID_3") (pintype "bidirectional"))
      (node (ref "U4") (pin "5") (pinfunction "GND_5") (pintype "bidirectional"))
      (node (ref "U4") (pin "9") (pinfunction "GND_9") (pintype "bidirectional"))
      (node (ref "U5") (pin "6") (pinfunction "GND_6") (pintype "bidirectional"))
      (node (ref "U5") (pin "GND1") (pinfunction "SHIELD_GND1") (pintype "bidirectional"))
      (node (ref "U5") (pin "GND3") (pinfunction "SHIELD_GND3") (pintype "bidirectional"))
      (node (ref "U6") (pin "15") (pinfunction "GND_15") (pintype "bidirectional"))
      (node (ref "U7") (pin "1") (pinfunction "PGND_1") (pintype "bidirectional"))
      (node (ref "U7") (pin "3") (pinfunction "AGND_3") (pintype "bidirectional"))
      (node (ref "U7") (pin "6") (pinfunction "PG_6") (pintype "bidirectional"))
      (node (ref "U7") (pin "PAD") (pinfunction "PAD_PAD") (pintype "bidirectional"))
    )
    (net (code "67") (name "Net-(AG9805MT-VIN+1)") (class "Default")
      (node (ref "AG9805MT") (pin "P$5") (pinfunction "VIN+1_P$5") (pintype "input"))
      (node (ref "AG9805MT") (pin "P$6") (pinfunction "VIN+2_P$6") (pintype "input"))
      (node (ref "B1") (pin "+") (pinfunction "+_+") (pintype "passive"))
      (node (ref "B2") (pin "+") (pinfunction "+_+") (pintype "passive"))
      (node (ref "D1") (pin "C") (pinfunction "C_C") (pintype "passive"))
    )
    (net (code "68") (name "Net-(AG9805MT-VIN-1)") (class "Default")
      (node (ref "AG9805MT") (pin "P$7") (pinfunction "VIN-1_P$7") (pintype "input"))
      (node (ref "AG9805MT") (pin "P$8") (pinfunction "VIN-2_P$8") (pintype "input"))
      (node (ref "B1") (pin "-") (pinfunction "-_-") (pintype "passive"))
      (node (ref "B2") (pin "-") (pinfunction "-_-") (pintype "passive"))
      (node (ref "D1") (pin "A") (pinfunction "A_A") (pintype "passive"))
    )
    (net (code "69") (name "Net-(D2-PadC)") (class "Default")
      (node (ref "D2") (pin "C") (pinfunction "C_C") (pintype "passive"))
      (node (ref "R19") (pin "2") (pinfunction "2_2") (pintype "passive"))
    )
    (net (code "70") (name "Net-(LED1-PadC)") (class "Default")
      (node (ref "LED1") (pin "C") (pinfunction "C_C") (pintype "passive"))
      (node (ref "R13") (pin "1") (pinfunction "1_1") (pintype "passive"))
    )
    (net (code "71") (name "Net-(R10-Pad1)") (class "Default")
      (node (ref "R10") (pin "1") (pinfunction "1_1") (pintype "passive"))
      (node (ref "RB1-125BHQ1A") (pin "S1") (pinfunction "S1_S1") (pintype "bidirectional"))
      (node (ref "RB1-125BHQ1A") (pin "S2") (pinfunction "S2_S2") (pintype "bidirectional"))
    )
    (net (code "72") (name "Net-(R11-Pad1)") (class "Default")
      (node (ref "R11") (pin "1") (pinfunction "1_1") (pintype "passive"))
      (node (ref "RB1-125BHQ1A") (pin "L2") (pinfunction "L2_L2") (pintype "output"))
    )
    (net (code "73") (name "Net-(R12-Pad1)") (class "Default")
      (node (ref "R12") (pin "1") (pinfunction "1_1") (pintype "passive"))
      (node (ref "RB1-125BHQ1A") (pin "L4") (pinfunction "L4_L4") (pintype "output"))
    )
    (net (code "74") (name "Net-(RB1-125BHQ1A-RD+)") (class "Default")
      (node (ref "C22") (pin "1") (pinfunction "1_1") (pintype "passive"))
      (node (ref "R8") (pin "1") (pinfunction "1_1") (pintype "passive"))
      (node (ref "RB1-125BHQ1A") (pin "R1") (pinfunction "RD+_R1") (pintype "output"))
      (node (ref "U2") (pin "52") (pinfunction "RXP_52") (pintype "passive"))
    )
    (net (code "75") (name "Net-(RB1-125BHQ1A-RD-)") (class "Default")
      (node (ref "C21") (pin "1") (pinfunction "1_1") (pintype "passive"))
      (node (ref "R7") (pin "1") (pinfunction "1_1") (pintype "passive"))
      (node (ref "RB1-125BHQ1A") (pin "R2") (pinfunction "RD-_R2") (pintype "output"))
      (node (ref "U2") (pin "53") (pinfunction "RXN_53") (pintype "passive"))
    )
    (net (code "76") (name "Net-(RB1-125BHQ1A-TCT)") (class "Default")
      (node (ref "C23") (pin "1") (pinfunction "1_1") (pintype "passive"))
      (node (ref "R9") (pin "1") (pinfunction "1_1") (pintype "passive"))
      (node (ref "RB1-125BHQ1A") (pin "R3") (pinfunction "TCT_R3") (pintype "output"))
    )
    (net (code "77") (name "Net-(RB1-125BHQ1A-TD+)") (class "Default")
      (node (ref "C20") (pin "1") (pinfunction "1_1") (pintype "passive"))
      (node (ref "R6") (pin "1") (pinfunction "1_1") (pintype "passive"))
      (node (ref "RB1-125BHQ1A") (pin "R5") (pinfunction "TD+_R5") (pintype "output"))
      (node (ref "U2") (pin "55") (pinfunction "TXP_55") (pintype "passive"))
    )
    (net (code "78") (name "Net-(RB1-125BHQ1A-TD-)") (class "Default")
      (node (ref "C19") (pin "1") (pinfunction "1_1") (pintype "passive"))
      (node (ref "R5") (pin "1") (pinfunction "1_1") (pintype "passive"))
      (node (ref "RB1-125BHQ1A") (pin "R4") (pinfunction "TD-_R4") (pintype "output"))
      (node (ref "U2") (pin "56") (pinfunction "TXN_56") (pintype "passive"))
    )
    (net (code "79") (name "Net-(U$1-1)") (class "Default")
      (node (ref "C25") (pin "1") (pinfunction "1_1") (pintype "passive"))
      (node (ref "R14") (pin "2") (pinfunction "2_2") (pintype "passive"))
      (node (ref "U$1") (pin "3") (pinfunction "1_3") (pintype "passive"))
      (node (ref "U2") (pin "60") (pinfunction "XO_60") (pintype "passive"))
    )
    (net (code "80") (name "Net-(U$1-2)") (class "Default")
      (node (ref "C24") (pin "1") (pinfunction "1_1") (pintype "passive"))
      (node (ref "R14") (pin "1") (pinfunction "1_1") (pintype "passive"))
      (node (ref "U$1") (pin "1") (pinfunction "2_1") (pintype "passive"))
      (node (ref "U2") (pin "61") (pinfunction "XI_61") (pintype "passive"))
    )
    (net (code "81") (name "Net-(U2-AUTOMDIX_EN)") (class "Default")
      (node (ref "R4") (pin "1") (pinfunction "1_1") (pintype "passive"))
      (node (ref "U2") (pin "41") (pinfunction "AUTOMDIX_EN_41") (pintype "passive"))
    )
    (net (code "82") (name "Net-(U2-CLK24_EN)") (class "Default")
      (node (ref "R17") (pin "1") (pinfunction "1_1") (pintype "passive"))
      (node (ref "U2") (pin "44") (pinfunction "CLK24_EN_44") (pintype "passive"))
    )
    (net (code "83") (name "Net-(U2-EXRES)") (class "Default")
      (node (ref "R3") (pin "1") (pinfunction "1_1") (pintype "passive"))
      (node (ref "U2") (pin "50") (pinfunction "EXRES_50") (pintype "passive"))
    )
    (net (code "84") (name "Net-(U2-NFDX_LED{slash}GPIO0)") (class "Default")
      (node (ref "R13") (pin "2") (pinfunction "2_2") (pintype "passive"))
      (node (ref "U2") (pin "20") (pinfunction "NFDX_LED/GPIO0_20") (pintype "bidirectional"))
    )
    (net (code "85") (name "Net-(U2-NLNKA_LED{slash}GPIO1)") (class "Default")
      (node (ref "R11") (pin "2") (pinfunction "2_2") (pintype "passive"))
      (node (ref "U2") (pin "21") (pinfunction "NLNKA_LED/GPIO1_21") (pintype "bidirectional"))
    )
    (net (code "86") (name "Net-(U2-NRESET)") (class "Default")
      (node (ref "C18") (pin "1") (pinfunction "1_1") (pintype "passive"))
      (node (ref "R1") (pin "1") (pinfunction "1_1") (pintype "passive"))
      (node (ref "U2") (pin "12") (pinfunction "NRESET_12") (pintype "passive"))
    )
    (net (code "87") (name "Net-(U2-NSPD_LED{slash}GPIO2)") (class "Default")
      (node (ref "R12") (pin "2") (pinfunction "2_2") (pintype "passive"))
      (node (ref "U2") (pin "22") (pinfunction "NSPD_LED/GPIO2_22") (pintype "bidirectional"))
    )
    (net (code "88") (name "Net-(U2-PRTCTL2)") (class "Default")
      (node (ref "U2") (pin "14") (pinfunction "PRTCTL2_14") (pintype "passive"))
      (node (ref "U3") (pin "4") (pinfunction "ON_4") (pintype "input"))
      (node (ref "U3") (pin "6") (pinfunction "*FLAG_6") (pintype "output"))
    )
    (net (code "89") (name "Net-(U2-USBDM2)") (class "Default")
      (node (ref "JP2") (pin "D-") (pinfunction "D-_D-") (pintype "bidirectional"))
      (node (ref "U2") (pin "1") (pinfunction "USBDM2_1") (pintype "passive"))
    )
    (net (code "90") (name "Net-(U2-USBDP2)") (class "Default")
      (node (ref "JP2") (pin "D+") (pinfunction "D+_D+") (pintype "bidirectional"))
      (node (ref "U2") (pin "2") (pinfunction "USBDP2_2") (pintype "passive"))
    )
    (net (code "91") (name "Net-(U2-USBRBIAS)") (class "Default")
      (node (ref "R2") (pin "1") (pinfunction "1_1") (pintype "passive"))
      (node (ref "U2") (pin "63") (pinfunction "USBRBIAS_63") (pintype "passive"))
    )
    (net (code "92") (name "Net-(U3-OUT)") (class "Default")
      (node (ref "C26") (pin "+") (pinfunction "+_+") (pintype "passive"))
      (node (ref "JP2") (pin "VBUS") (pinfunction "VBUS_VBUS") (pintype "bidirectional"))
      (node (ref "U3") (pin "1") (pinfunction "OUT_1") (pintype "output"))
    )
    (net (code "93") (name "Net-(U3-SETI)") (class "Default")
      (node (ref "R15") (pin "2") (pinfunction "2_2") (pintype "passive"))
      (node (ref "U3") (pin "3") (pinfunction "SETI_3") (pintype "passive"))
    )
    (net (code "94") (name "Net-(U5-CS)") (class "Default")
      (node (ref "U5") (pin "2") (pinfunction "CS_2") (pintype "bidirectional"))
      (node (ref "U6") (pin "19") (pinfunction "B2_19") (pintype "bidirectional"))
    )
    (net (code "95") (name "Net-(U5-DI)") (class "Default")
      (node (ref "U5") (pin "3") (pinfunction "DI_3") (pintype "bidirectional"))
      (node (ref "U6") (pin "18") (pinfunction "B3_18") (pintype "bidirectional"))
    )
    (net (code "96") (name "Net-(U5-DO)") (class "Default")
      (node (ref "U5") (pin "7") (pinfunction "DO_7") (pintype "bidirectional"))
      (node (ref "U6") (pin "14") (pinfunction "B5_14") (pintype "bidirectional"))
    )
    (net (code "97") (name "Net-(U5-NC)") (class "Default")
      (node (ref "U5") (pin "1") (pinfunction "NC_1") (pintype "bidirectional"))
      (node (ref "U6") (pin "20") (pinfunction "B1_20") (pintype "bidirectional"))
    )
    (net (code "98") (name "Net-(U5-RSV)") (class "Default")
      (node (ref "U5") (pin "8") (pinfunction "RSV_8") (pintype "bidirectional"))
      (node (ref "U6") (pin "13") (pinfunction "B6_13") (pintype "bidirectional"))
    )
    (net (code "99") (name "Net-(U5-SCK)") (class "Default")
      (node (ref "U5") (pin "5") (pinfunction "SCK_5") (pintype "bidirectional"))
      (node (ref "U6") (pin "12") (pinfunction "B7_12") (pintype "bidirectional"))
      (node (ref "U6") (pin "17") (pinfunction "B4_17") (pintype "bidirectional"))
    )
    (net (code "100") (name "Net-(U7-FB)") (class "Default")
      (node (ref "C35") (pin "2") (pinfunction "2_2") (pintype "passive"))
      (node (ref "R16") (pin "1") (pinfunction "1_1") (pintype "passive"))
      (node (ref "R18") (pin "2") (pinfunction "2_2") (pintype "passive"))
      (node (ref "U7") (pin "4") (pinfunction "FB_4") (pintype "bidirectional"))
    )
    (net (code "101") (name "Net-(U7-SW)") (class "Default")
      (node (ref "L3") (pin "1") (pinfunction "1_1") (pintype "passive"))
      (node (ref "U7") (pin "2") (pinfunction "SW_2") (pintype "bidirectional"))
    )
    (net (code "102") (name "VDD") (class "Default")
      (node (ref "C10") (pin "1") (pinfunction "1_1") (pintype "passive"))
      (node (ref "C11") (pin "1") (pinfunction "1_1") (pintype "passive"))
      (node (ref "C12") (pin "1") (pinfunction "1_1") (pintype "passive"))
      (node (ref "C6") (pin "1") (pinfunction "1_1") (pintype "passive"))
      (node (ref "C7") (pin "1") (pinfunction "1_1") (pintype "passive"))
      (node (ref "C8") (pin "1") (pinfunction "1_1") (pintype "passive"))
      (node (ref "C9") (pin "1") (pinfunction "1_1") (pintype "passive"))
      (node (ref "L1") (pin "2") (pinfunction "2_2") (pintype "passive"))
      (node (ref "R5") (pin "2") (pinfunction "2_2") (pintype "passive"))
      (node (ref "R6") (pin "2") (pinfunction "2_2") (pintype "passive"))
      (node (ref "R7") (pin "2") (pinfunction "2_2") (pintype "passive"))
      (node (ref "R8") (pin "2") (pinfunction "2_2") (pintype "passive"))
      (node (ref "R9") (pin "2") (pinfunction "2_2") (pintype "passive"))
      (node (ref "U2") (pin "10") (pinfunction "VDD33A_3_10") (pintype "power_in"))
      (node (ref "U2") (pin "49") (pinfunction "VDD33A_4_49") (pintype "power_in"))
      (node (ref "U2") (pin "5") (pinfunction "VDD33A_2_5") (pintype "power_in"))
      (node (ref "U2") (pin "51") (pinfunction "VDD33A_5_51") (pintype "power_in"))
      (node (ref "U2") (pin "54") (pinfunction "VDD33A_6_54") (pintype "power_in"))
      (node (ref "U2") (pin "57") (pinfunction "VDD33A_7_57") (pintype "power_in"))
      (node (ref "U2") (pin "64") (pinfunction "VDD33A_64") (pintype "power_in"))
    )
    (net (code "103") (name "unconnected-(AG9805MT-ADJ-PadP$4)") (class "Default")
      (node (ref "AG9805MT") (pin "P$4") (pinfunction "ADJ_P$4") (pintype "bidirectional"))
    )
    (net (code "104") (name "unconnected-(U2-EECLK-Pad23)") (class "Default")
      (node (ref "U2") (pin "23") (pinfunction "EECLK_23") (pintype "passive"))
    )
    (net (code "105") (name "unconnected-(U2-EECS-Pad24)") (class "Default")
      (node (ref "U2") (pin "24") (pinfunction "EECS_24") (pintype "passive"))
    )
    (net (code "106") (name "unconnected-(U2-EEDI-Pad26)") (class "Default")
      (node (ref "U2") (pin "26") (pinfunction "EEDI_26") (pintype "passive"))
    )
    (net (code "107") (name "unconnected-(U2-EEDO-Pad25)") (class "Default")
      (node (ref "U2") (pin "25") (pinfunction "EEDO_25") (pintype "passive"))
    )
    (net (code "108") (name "unconnected-(U2-GPIO3-Pad35)") (class "Default")
      (node (ref "U2") (pin "35") (pinfunction "GPIO3_35") (pintype "bidirectional"))
    )
    (net (code "109") (name "unconnected-(U2-GPIO4-Pad36)") (class "Default")
      (node (ref "U2") (pin "36") (pinfunction "GPIO4_36") (pintype "bidirectional"))
    )
    (net (code "110") (name "unconnected-(U2-GPIO5-Pad37)") (class "Default")
      (node (ref "U2") (pin "37") (pinfunction "GPIO5_37") (pintype "bidirectional"))
    )
    (net (code "111") (name "unconnected-(U2-GPIO6-Pad42)") (class "Default")
      (node (ref "U2") (pin "42") (pinfunction "GPIO6_42") (pintype "bidirectional"))
    )
    (net (code "112") (name "unconnected-(U2-GPIO7-Pad43)") (class "Default")
      (node (ref "U2") (pin "43") (pinfunction "GPIO7_43") (pintype "bidirectional"))
    )
    (net (code "113") (name "unconnected-(U2-NC-Pad18)") (class "Default")
      (node (ref "U2") (pin "18") (pinfunction "NC_18") (pintype "no_connect"))
    )
    (net (code "114") (name "unconnected-(U2-NC_2-Pad6)") (class "Default")
      (node (ref "U2") (pin "6") (pinfunction "NC_2_6") (pintype "no_connect"))
    )
    (net (code "115") (name "unconnected-(U2-NC_3-Pad7)") (class "Default")
      (node (ref "U2") (pin "7") (pinfunction "NC_3_7") (pintype "no_connect"))
    )
    (net (code "116") (name "unconnected-(U2-NC_4-Pad8)") (class "Default")
      (node (ref "U2") (pin "8") (pinfunction "NC_4_8") (pintype "no_connect"))
    )
    (net (code "117") (name "unconnected-(U2-NC_5-Pad9)") (class "Default")
      (node (ref "U2") (pin "9") (pinfunction "NC_5_9") (pintype "no_connect"))
    )
    (net (code "118") (name "unconnected-(U2-NC_6-Pad17)") (class "Default")
      (node (ref "U2") (pin "17") (pinfunction "NC_6_17") (pintype "no_connect"))
    )
    (net (code "119") (name "unconnected-(U2-PRTCTL3-Pad16)") (class "Default")
      (node (ref "U2") (pin "16") (pinfunction "PRTCTL3_16") (pintype "passive"))
    )
    (net (code "120") (name "unconnected-(U2-TDO-Pad31)") (class "Default")
      (node (ref "U2") (pin "31") (pinfunction "TDO_31") (pintype "passive"))
    )
    (net (code "121") (name "unconnected-(U2-TEST1-Pad13)") (class "Default")
      (node (ref "U2") (pin "13") (pinfunction "TEST1_13") (pintype "passive"))
    )
    (net (code "122") (name "unconnected-(U2-TEST4-Pad47)") (class "Default")
      (node (ref "U2") (pin "47") (pinfunction "TEST4_47") (pintype "passive"))
    )
    (net (code "123") (name "unconnected-(U5-PadCD2)") (class "Default")
      (node (ref "U5") (pin "CD2") (pinfunction "CD2_CD2") (pintype "bidirectional"))
    )
    (net (code "124") (name "unconnected-(U6-A8-Pad10)") (class "Default")
      (node (ref "U6") (pin "10") (pinfunction "A8_10") (pintype "bidirectional"))
    )
    (net (code "125") (name "unconnected-(U6-B8-Pad11)") (class "Default")
      (node (ref "U6") (pin "11") (pinfunction "B8_11") (pintype "bidirectional"))
    )
  )
)
